# HighLevel.net
KiCad netlist of a schematic drawn in EAGLE
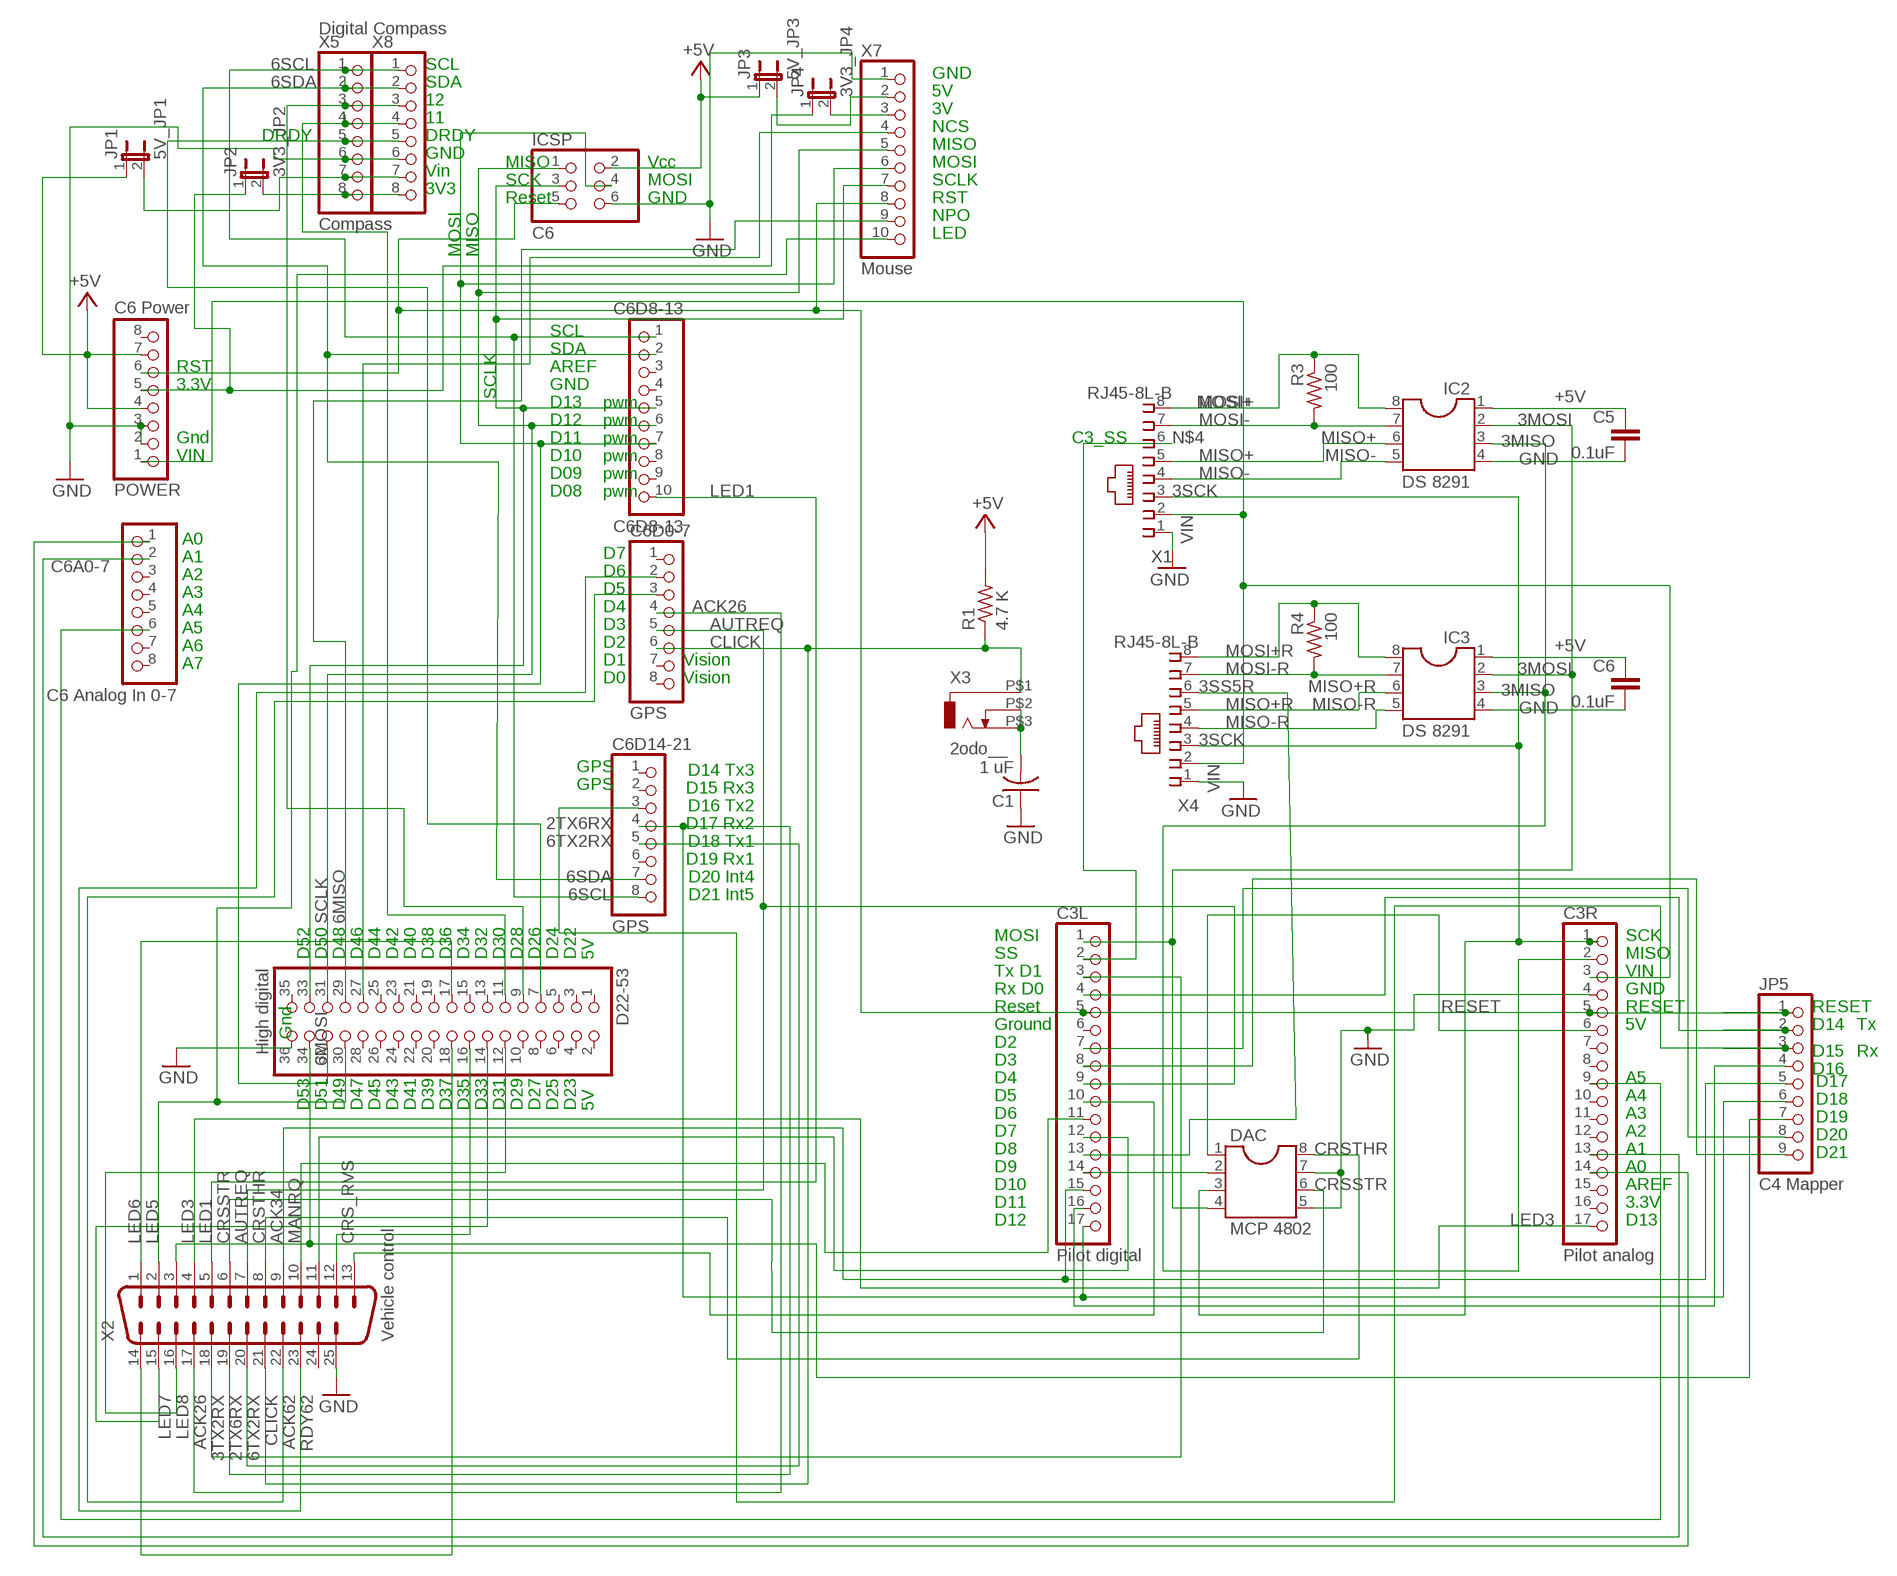
[diagram p0: schematic, sheet 1]

(export (version "E")
  (design (tool "Eeschema 10.0.6"))
  (components
    (comp (ref "C1")
      (value "1 uF")
      (footprint "eagle-import:C025-030X050")
      (libsource (lib "eagle-import") (part "C-US025-030X050"))
    )
    (comp (ref "C3L")
      (value "Pilot digital")
      (footprint "eagle-import:1X17")
      (libsource (lib "eagle-import") (part "PINHD-1X17"))
    )
    (comp (ref "C3R")
      (value "Pilot analog")
      (footprint "eagle-import:1X17")
      (libsource (lib "eagle-import") (part "PINHD-1X17"))
    )
    (comp (ref "C5")
      (value "0.1uF")
      (footprint "eagle-import:C2.5-2")
      (libsource (lib "eagle-import") (part "C2.5/2"))
    )
    (comp (ref "C6")
      (value "0.1uF")
      (footprint "eagle-import:C2.5-2")
      (libsource (lib "eagle-import") (part "C2.5/2"))
    )
    (comp (ref "C6A0-7")
      (value "C6 Analog In 0-7")
      (footprint "eagle-import:1X08")
      (libsource (lib "eagle-import") (part "PINHD-1X8"))
    )
    (comp (ref "C6D0-7")
      (value "GPS")
      (footprint "eagle-import:1X08")
      (libsource (lib "eagle-import") (part "PINHD-1X8"))
    )
    (comp (ref "C6D8-13")
      (value "C6D8-13")
      (footprint "eagle-import:1X10")
      (libsource (lib "eagle-import") (part "PINHD-1X10"))
    )
    (comp (ref "C6D14-21")
      (value "GPS")
      (footprint "eagle-import:1X08")
      (libsource (lib "eagle-import") (part "PINHD-1X8"))
    )
    (comp (ref "D22-53")
      (value "High digital")
      (footprint "eagle-import:2X18")
      (libsource (lib "eagle-import") (part "PINHD-2X18"))
    )
    (comp (ref "DAC")
      (value "MCP 4802")
      (footprint "eagle-import:DIL08")
      (libsource (lib "eagle-import") (part "DIL8"))
    )
    (comp (ref "IC2")
      (value "DS 8291")
      (footprint "eagle-import:DIL08")
      (libsource (lib "eagle-import") (part "DIL8"))
    )
    (comp (ref "IC3")
      (value "DS 8291")
      (footprint "eagle-import:DIL08")
      (libsource (lib "eagle-import") (part "DIL8"))
    )
    (comp (ref "ICSP")
      (value "C6")
      (footprint "eagle-import:2X03")
      (libsource (lib "eagle-import") (part "PINHD-2X3"))
    )
    (comp (ref "JP1")
      (value "5V_JP1")
      (footprint "eagle-import:JP1")
      (libsource (lib "eagle-import") (part "JP1E"))
    )
    (comp (ref "JP2")
      (value "3V3_JP2")
      (footprint "eagle-import:JP1")
      (libsource (lib "eagle-import") (part "JP1E"))
    )
    (comp (ref "JP3")
      (value "5V_JP3")
      (footprint "eagle-import:JP1")
      (libsource (lib "eagle-import") (part "JP1E"))
    )
    (comp (ref "JP4")
      (value "3V3_JP4")
      (footprint "eagle-import:JP1")
      (libsource (lib "eagle-import") (part "JP1E"))
    )
    (comp (ref "JP5")
      (value "C4 Mapper")
      (footprint "eagle-import:1X09")
      (libsource (lib "eagle-import") (part "PINHD-1X9"))
    )
    (comp (ref "POWER")
      (value "C6 Power")
      (footprint "eagle-import:1X08")
      (libsource (lib "eagle-import") (part "PINHD-1X8"))
    )
    (comp (ref "R1")
      (value "4.7 K")
      (footprint "eagle-import:0207_10")
      (libsource (lib "eagle-import") (part "R-US_0207/10"))
    )
    (comp (ref "R3")
      (value "100")
      (footprint "eagle-import:0204_5")
      (libsource (lib "eagle-import") (part "resistor_R-US_0204/5"))
    )
    (comp (ref "R4")
      (value "100")
      (footprint "eagle-import:0204_5")
      (libsource (lib "eagle-import") (part "resistor_R-US_0204/5"))
    )
    (comp (ref "X1")
      (value "RJ45-8L-B")
      (footprint "eagle-import:RJ45-NO-SHIELD")
      (fields (field (name "MF") "TYCO ELECTRONICS"))
      (libsource (lib "eagle-import") (part "RJ45-8L-B"))
    )
    (comp (ref "X2")
      (value "Vehicle control")
      (footprint "eagle-import:M25H")
      (libsource (lib "eagle-import") (part "M25H"))
    )
    (comp (ref "X3")
      (value "2odo__")
      (footprint "eagle-import:ODO_JACK")
      (libsource (lib "eagle-import") (part "ODO_JACK"))
    )
    (comp (ref "X4")
      (value "RJ45-8L-B")
      (footprint "eagle-import:RJ45-NO-SHIELD")
      (fields (field (name "MF") "TYCO ELECTRONICS"))
      (libsource (lib "eagle-import") (part "RJ45-8L-B"))
    )
    (comp (ref "X5")
      (value "Compass")
      (footprint "eagle-import:1X08")
      (libsource (lib "eagle-import") (part "PINHD-1X8"))
    )
    (comp (ref "X7")
      (value "Mouse")
      (footprint "eagle-import:1X10")
      (libsource (lib "eagle-import") (part "PINHD-1X10"))
    )
    (comp (ref "X8")
      (value "Digital Compass")
      (footprint "eagle-import:1X08")
      (libsource (lib "eagle-import") (part "PINHD-1X8"))
    )
  )
  (nets
    (net (code "1") (name "+5V") (class "Default")
      (node (ref "C5") (pin "1") (pinfunction "1_1") (pintype "passive"))
      (node (ref "C6") (pin "1") (pinfunction "1_1") (pintype "passive"))
      (node (ref "IC2") (pin "1") (pinfunction "1_1") (pintype "passive"))
      (node (ref "IC3") (pin "1") (pinfunction "1_1") (pintype "passive"))
      (node (ref "ICSP") (pin "2") (pinfunction "2_2") (pintype "passive"))
      (node (ref "JP1") (pin "1") (pinfunction "1_1") (pintype "passive"))
      (node (ref "JP3") (pin "1") (pinfunction "1_1") (pintype "passive"))
      (node (ref "POWER") (pin "4") (pinfunction "4_4") (pintype "passive"))
      (node (ref "POWER") (pin "7") (pinfunction "7_7") (pintype "passive"))
      (node (ref "R1") (pin "2") (pinfunction "2_2") (pintype "passive"))
    )
    (net (code "2") (name "2TX6RX") (class "Default")
      (node (ref "C3L") (pin "17") (pinfunction "17_17") (pintype "passive"))
      (node (ref "C6D14-21") (pin "4") (pinfunction "4_4") (pintype "passive"))
      (node (ref "JP5") (pin "6") (pinfunction "6_6") (pintype "passive"))
      (node (ref "X2") (pin "19") (pinfunction "19_19") (pintype "passive"))
    )
    (net (code "3") (name "3MISO") (class "Default")
      (node (ref "C3R") (pin "2") (pinfunction "2_2") (pintype "passive"))
      (node (ref "IC2") (pin "3") (pinfunction "3_3") (pintype "passive"))
      (node (ref "IC3") (pin "3") (pinfunction "3_3") (pintype "passive"))
    )
    (net (code "4") (name "3MOSI") (class "Default")
      (node (ref "C3L") (pin "1") (pinfunction "1_1") (pintype "passive"))
      (node (ref "DAC") (pin "4") (pinfunction "4_4") (pintype "passive"))
      (node (ref "IC2") (pin "2") (pinfunction "2_2") (pintype "passive"))
      (node (ref "IC3") (pin "2") (pinfunction "2_2") (pintype "passive"))
    )
    (net (code "5") (name "3SCK") (class "Default")
      (node (ref "C3R") (pin "1") (pinfunction "1_1") (pintype "passive"))
      (node (ref "DAC") (pin "3") (pinfunction "3_3") (pintype "passive"))
      (node (ref "X1") (pin "3") (pinfunction "3_3") (pintype "passive"))
      (node (ref "X4") (pin "3") (pinfunction "3_3") (pintype "passive"))
    )
    (net (code "6") (name "3SS5R") (class "Default")
      (node (ref "C3L") (pin "13") (pinfunction "13_13") (pintype "passive"))
      (node (ref "X4") (pin "6") (pinfunction "6_6") (pintype "passive"))
    )
    (net (code "7") (name "3TX2RX") (class "Default")
      (node (ref "C3L") (pin "3") (pinfunction "3_3") (pintype "passive"))
      (node (ref "X2") (pin "18") (pinfunction "18_18") (pintype "passive"))
    )
    (net (code "8") (name "6MISO") (class "Default")
      (node (ref "C6D8-13") (pin "6") (pinfunction "6_6") (pintype "passive"))
      (node (ref "D22-53") (pin "31") (pinfunction "31_31") (pintype "passive"))
      (node (ref "ICSP") (pin "1") (pinfunction "1_1") (pintype "passive"))
      (node (ref "X7") (pin "5") (pinfunction "5_5") (pintype "passive"))
    )
    (net (code "9") (name "6MOSI") (class "Default")
      (node (ref "C6D8-13") (pin "7") (pinfunction "7_7") (pintype "passive"))
      (node (ref "D22-53") (pin "32") (pinfunction "32_32") (pintype "passive"))
      (node (ref "ICSP") (pin "4") (pinfunction "4_4") (pintype "passive"))
      (node (ref "X7") (pin "6") (pinfunction "6_6") (pintype "passive"))
    )
    (net (code "10") (name "6SCL") (class "Default")
      (node (ref "C6D14-21") (pin "8") (pinfunction "8_8") (pintype "passive"))
      (node (ref "C6D8-13") (pin "1") (pinfunction "1_1") (pintype "passive"))
      (node (ref "X5") (pin "1") (pinfunction "1_1") (pintype "passive"))
      (node (ref "X8") (pin "1") (pinfunction "1_1") (pintype "passive"))
    )
    (net (code "11") (name "6SDA") (class "Default")
      (node (ref "C6D14-21") (pin "7") (pinfunction "7_7") (pintype "passive"))
      (node (ref "C6D8-13") (pin "2") (pinfunction "2_2") (pintype "passive"))
      (node (ref "X5") (pin "2") (pinfunction "2_2") (pintype "passive"))
      (node (ref "X8") (pin "2") (pinfunction "2_2") (pintype "passive"))
    )
    (net (code "12") (name "6TX2RX") (class "Default")
      (node (ref "C6D14-21") (pin "5") (pinfunction "5_5") (pintype "passive"))
      (node (ref "X2") (pin "20") (pinfunction "20_20") (pintype "passive"))
    )
    (net (code "13") (name "ACK26") (class "Default")
      (node (ref "C6D0-7") (pin "4") (pinfunction "4_4") (pintype "passive"))
      (node (ref "X2") (pin "17") (pinfunction "17_17") (pintype "passive"))
    )
    (net (code "14") (name "ACK34") (class "Default")
      (node (ref "C3L") (pin "15") (pinfunction "15_15") (pintype "passive"))
      (node (ref "JP5") (pin "5") (pinfunction "5_5") (pintype "passive"))
      (node (ref "X2") (pin "9") (pinfunction "9_9") (pintype "passive"))
    )
    (net (code "15") (name "ACK62") (class "Default")
      (node (ref "C6D0-7") (pin "3") (pinfunction "3_3") (pintype "passive"))
      (node (ref "X2") (pin "22") (pinfunction "22_22") (pintype "passive"))
    )
    (net (code "16") (name "AUTREQ") (class "Default")
      (node (ref "C3L") (pin "9") (pinfunction "9_9") (pintype "passive"))
      (node (ref "C6D0-7") (pin "5") (pinfunction "5_5") (pintype "passive"))
      (node (ref "X2") (pin "7") (pinfunction "7_7") (pintype "passive"))
    )
    (net (code "17") (name "CLICK") (class "Default")
      (node (ref "C6D0-7") (pin "6") (pinfunction "6_6") (pintype "passive"))
      (node (ref "R1") (pin "1") (pinfunction "1_1") (pintype "passive"))
      (node (ref "X2") (pin "21") (pinfunction "21_21") (pintype "passive"))
      (node (ref "X3") (pin "P$1") (pinfunction "1_P$1") (pintype "passive"))
    )
    (net (code "18") (name "CRSSTR") (class "Default")
      (node (ref "DAC") (pin "6") (pinfunction "6_6") (pintype "passive"))
      (node (ref "X2") (pin "6") (pinfunction "6_6") (pintype "passive"))
    )
    (net (code "19") (name "CRSTHR") (class "Default")
      (node (ref "DAC") (pin "8") (pinfunction "8_8") (pintype "passive"))
      (node (ref "X2") (pin "8") (pinfunction "8_8") (pintype "passive"))
    )
    (net (code "20") (name "CRS_RVS") (class "Default")
      (node (ref "C3L") (pin "10") (pinfunction "10_10") (pintype "passive"))
      (node (ref "X2") (pin "13") (pinfunction "13_13") (pintype "passive"))
    )
    (net (code "21") (name "GND") (class "Default")
      (node (ref "C1") (pin "1") (pinfunction "1_1") (pintype "passive"))
      (node (ref "C3R") (pin "4") (pinfunction "4_4") (pintype "passive"))
      (node (ref "C5") (pin "2") (pinfunction "2_2") (pintype "passive"))
      (node (ref "C6") (pin "2") (pinfunction "2_2") (pintype "passive"))
      (node (ref "D22-53") (pin "36") (pinfunction "36_36") (pintype "passive"))
      (node (ref "DAC") (pin "5") (pinfunction "5_5") (pintype "passive"))
      (node (ref "DAC") (pin "7") (pinfunction "7_7") (pintype "passive"))
      (node (ref "IC2") (pin "4") (pinfunction "4_4") (pintype "passive"))
      (node (ref "IC3") (pin "4") (pinfunction "4_4") (pintype "passive"))
      (node (ref "ICSP") (pin "6") (pinfunction "6_6") (pintype "passive"))
      (node (ref "POWER") (pin "2") (pinfunction "2_2") (pintype "passive"))
      (node (ref "POWER") (pin "3") (pinfunction "3_3") (pintype "passive"))
      (node (ref "X1") (pin "1") (pinfunction "1_1") (pintype "passive"))
      (node (ref "X2") (pin "25") (pinfunction "25_25") (pintype "passive"))
      (node (ref "X4") (pin "1") (pinfunction "1_1") (pintype "passive"))
      (node (ref "X5") (pin "6") (pinfunction "6_6") (pintype "passive"))
      (node (ref "X7") (pin "1") (pinfunction "1_1") (pintype "passive"))
      (node (ref "X8") (pin "6") (pinfunction "6_6") (pintype "passive"))
    )
    (net (code "22") (name "LED1") (class "Default")
      (node (ref "C6D8-13") (pin "10") (pinfunction "10_10") (pintype "passive"))
      (node (ref "X2") (pin "5") (pinfunction "5_5") (pintype "passive"))
    )
    (net (code "23") (name "LED3") (class "Default")
      (node (ref "C3R") (pin "17") (pinfunction "17_17") (pintype "passive"))
      (node (ref "X2") (pin "4") (pinfunction "4_4") (pintype "passive"))
    )
    (net (code "24") (name "LED5") (class "Default")
      (node (ref "D22-53") (pin "30") (pinfunction "30_30") (pintype "passive"))
      (node (ref "X2") (pin "2") (pinfunction "2_2") (pintype "passive"))
      (node (ref "X7") (pin "10") (pinfunction "10_10") (pintype "passive"))
    )
    (net (code "25") (name "LED6") (class "Default")
      (node (ref "D22-53") (pin "17") (pinfunction "17_17") (pintype "passive"))
      (node (ref "X2") (pin "1") (pinfunction "1_1") (pintype "passive"))
    )
    (net (code "26") (name "LED7") (class "Default")
      (node (ref "D22-53") (pin "14") (pinfunction "14_14") (pintype "passive"))
      (node (ref "X2") (pin "15") (pinfunction "15_15") (pintype "passive"))
    )
    (net (code "27") (name "LED8") (class "Default")
      (node (ref "D22-53") (pin "12") (pinfunction "12_12") (pintype "passive"))
      (node (ref "X2") (pin "16") (pinfunction "16_16") (pintype "passive"))
    )
    (net (code "28") (name "MANRQ") (class "Default")
      (node (ref "C3L") (pin "11") (pinfunction "11_11") (pintype "passive"))
      (node (ref "X2") (pin "10") (pinfunction "10_10") (pintype "passive"))
    )
    (net (code "29") (name "MISO+") (class "Default")
      (node (ref "IC2") (pin "6") (pinfunction "6_6") (pintype "passive"))
      (node (ref "X1") (pin "5") (pinfunction "5_5") (pintype "passive"))
    )
    (net (code "30") (name "MISO+R") (class "Default")
      (node (ref "IC3") (pin "6") (pinfunction "6_6") (pintype "passive"))
      (node (ref "X4") (pin "5") (pinfunction "5_5") (pintype "passive"))
    )
    (net (code "31") (name "MISO-") (class "Default")
      (node (ref "IC2") (pin "5") (pinfunction "5_5") (pintype "passive"))
      (node (ref "X1") (pin "4") (pinfunction "4_4") (pintype "passive"))
    )
    (net (code "32") (name "MISO-R") (class "Default")
      (node (ref "IC3") (pin "5") (pinfunction "5_5") (pintype "passive"))
      (node (ref "X4") (pin "4") (pinfunction "4_4") (pintype "passive"))
    )
    (net (code "33") (name "MOSI+") (class "Default")
      (node (ref "IC2") (pin "8") (pinfunction "8_8") (pintype "passive"))
      (node (ref "R3") (pin "1") (pinfunction "1_1") (pintype "passive"))
      (node (ref "X1") (pin "8") (pinfunction "8_8") (pintype "passive"))
    )
    (net (code "34") (name "MOSI+R") (class "Default")
      (node (ref "IC3") (pin "8") (pinfunction "8_8") (pintype "passive"))
      (node (ref "R4") (pin "1") (pinfunction "1_1") (pintype "passive"))
      (node (ref "X4") (pin "8") (pinfunction "8_8") (pintype "passive"))
    )
    (net (code "35") (name "MOSI-") (class "Default")
      (node (ref "IC2") (pin "7") (pinfunction "7_7") (pintype "passive"))
      (node (ref "R3") (pin "2") (pinfunction "2_2") (pintype "passive"))
      (node (ref "X1") (pin "7") (pinfunction "7_7") (pintype "passive"))
    )
    (net (code "36") (name "MOSI-R") (class "Default")
      (node (ref "IC3") (pin "7") (pinfunction "7_7") (pintype "passive"))
      (node (ref "R4") (pin "2") (pinfunction "2_2") (pintype "passive"))
      (node (ref "X4") (pin "7") (pinfunction "7_7") (pintype "passive"))
    )
    (net (code "37") (name "N$4") (class "Default")
      (node (ref "C3L") (pin "2") (pinfunction "2_2") (pintype "passive"))
      (node (ref "X1") (pin "6") (pinfunction "6_6") (pintype "passive"))
    )
    (net (code "38") (name "Net-(C3L-Pad4)") (class "Default")
      (node (ref "C3L") (pin "4") (pinfunction "4_4") (pintype "passive"))
      (node (ref "JP5") (pin "2") (pinfunction "2_2") (pintype "passive"))
    )
    (net (code "39") (name "Net-(C3L-Pad7)") (class "Default")
      (node (ref "C3L") (pin "7") (pinfunction "7_7") (pintype "passive"))
      (node (ref "JP5") (pin "8") (pinfunction "8_8") (pintype "passive"))
    )
    (net (code "40") (name "Net-(C3L-Pad8)") (class "Default")
      (node (ref "C3L") (pin "8") (pinfunction "8_8") (pintype "passive"))
      (node (ref "JP5") (pin "9") (pinfunction "9_9") (pintype "passive"))
    )
    (net (code "41") (name "Net-(C3L-Pad12)") (class "Default")
      (node (ref "C3L") (pin "12") (pinfunction "12_12") (pintype "passive"))
      (node (ref "X2") (pin "11") (pinfunction "11_11") (pintype "passive"))
    )
    (net (code "42") (name "Net-(C3L-Pad14)") (class "Default")
      (node (ref "C3L") (pin "14") (pinfunction "14_14") (pintype "passive"))
      (node (ref "DAC") (pin "2") (pinfunction "2_2") (pintype "passive"))
    )
    (net (code "43") (name "Net-(C3L-Pad16)") (class "Default")
      (node (ref "C3L") (pin "16") (pinfunction "16_16") (pintype "passive"))
      (node (ref "JP5") (pin "4") (pinfunction "4_4") (pintype "passive"))
    )
    (net (code "44") (name "Net-(C3R-Pad6)") (class "Default")
      (node (ref "C3R") (pin "6") (pinfunction "6_6") (pintype "passive"))
      (node (ref "DAC") (pin "1") (pinfunction "1_1") (pintype "passive"))
    )
    (net (code "45") (name "Net-(C3R-Pad9)") (class "Default")
      (node (ref "C3R") (pin "9") (pinfunction "9_9") (pintype "passive"))
      (node (ref "C6A0-7") (pin "6") (pinfunction "6_6") (pintype "passive"))
    )
    (net (code "46") (name "Net-(C3R-Pad13)") (class "Default")
      (node (ref "C3R") (pin "13") (pinfunction "13_13") (pintype "passive"))
      (node (ref "C6A0-7") (pin "2") (pinfunction "2_2") (pintype "passive"))
    )
    (net (code "47") (name "Net-(C3R-Pad14)") (class "Default")
      (node (ref "C3R") (pin "14") (pinfunction "14_14") (pintype "passive"))
      (node (ref "C6A0-7") (pin "1") (pinfunction "1_1") (pintype "passive"))
    )
    (net (code "48") (name "Net-(C6D14-21-Pad3)") (class "Default")
      (node (ref "C6D14-21") (pin "3") (pinfunction "3_3") (pintype "passive"))
      (node (ref "JP5") (pin "3") (pinfunction "3_3") (pintype "passive"))
    )
    (net (code "49") (name "Net-(D22-53-Pad7)") (class "Default")
      (node (ref "D22-53") (pin "7") (pinfunction "7_7") (pintype "passive"))
      (node (ref "X5") (pin "5") (pinfunction "5_5") (pintype "passive"))
      (node (ref "X8") (pin "5") (pinfunction "5_5") (pintype "passive"))
    )
    (net (code "50") (name "Net-(D22-53-Pad9)") (class "Default")
      (node (ref "D22-53") (pin "9") (pinfunction "9_9") (pintype "passive"))
      (node (ref "X5") (pin "3") (pinfunction "3_3") (pintype "passive"))
      (node (ref "X8") (pin "3") (pinfunction "3_3") (pintype "passive"))
    )
    (net (code "51") (name "Net-(D22-53-Pad11)") (class "Default")
      (node (ref "D22-53") (pin "11") (pinfunction "11_11") (pintype "passive"))
      (node (ref "X5") (pin "4") (pinfunction "4_4") (pintype "passive"))
      (node (ref "X8") (pin "4") (pinfunction "4_4") (pintype "passive"))
    )
    (net (code "52") (name "Net-(D22-53-Pad16)") (class "Default")
      (node (ref "D22-53") (pin "16") (pinfunction "16_16") (pintype "passive"))
      (node (ref "X2") (pin "12") (pinfunction "12_12") (pintype "passive"))
    )
    (net (code "53") (name "Net-(D22-53-Pad18)") (class "Default")
      (node (ref "D22-53") (pin "18") (pinfunction "18_18") (pintype "passive"))
      (node (ref "X2") (pin "14") (pinfunction "14_14") (pintype "passive"))
    )
    (net (code "54") (name "Net-(D22-53-Pad27)") (class "Default")
      (node (ref "D22-53") (pin "27") (pinfunction "27_27") (pintype "passive"))
      (node (ref "X7") (pin "4") (pinfunction "4_4") (pintype "passive"))
    )
    (net (code "55") (name "Net-(D22-53-Pad29)") (class "Default")
      (node (ref "D22-53") (pin "29") (pinfunction "29_29") (pintype "passive"))
      (node (ref "X7") (pin "9") (pinfunction "9_9") (pintype "passive"))
    )
    (net (code "56") (name "Net-(D22-53-Pad34)") (class "Default")
      (node (ref "D22-53") (pin "34") (pinfunction "34_34") (pintype "passive"))
      (node (ref "JP5") (pin "7") (pinfunction "7_7") (pintype "passive"))
      (node (ref "X2") (pin "3") (pinfunction "3_3") (pintype "passive"))
    )
    (net (code "57") (name "Net-(JP1-Pad2)") (class "Default")
      (node (ref "JP1") (pin "2") (pinfunction "2_2") (pintype "passive"))
      (node (ref "X5") (pin "7") (pinfunction "7_7") (pintype "passive"))
      (node (ref "X8") (pin "7") (pinfunction "7_7") (pintype "passive"))
    )
    (net (code "58") (name "Net-(JP2-Pad1)") (class "Default")
      (node (ref "JP2") (pin "1") (pinfunction "1_1") (pintype "passive"))
      (node (ref "JP4") (pin "1") (pinfunction "1_1") (pintype "passive"))
      (node (ref "POWER") (pin "5") (pinfunction "5_5") (pintype "passive"))
    )
    (net (code "59") (name "Net-(JP2-Pad2)") (class "Default")
      (node (ref "JP2") (pin "2") (pinfunction "2_2") (pintype "passive"))
      (node (ref "X5") (pin "8") (pinfunction "8_8") (pintype "passive"))
      (node (ref "X8") (pin "8") (pinfunction "8_8") (pintype "passive"))
    )
    (net (code "60") (name "Net-(JP3-Pad2)") (class "Default")
      (node (ref "JP3") (pin "2") (pinfunction "2_2") (pintype "passive"))
      (node (ref "X7") (pin "2") (pinfunction "2_2") (pintype "passive"))
    )
    (net (code "61") (name "Net-(JP4-Pad2)") (class "Default")
      (node (ref "JP4") (pin "2") (pinfunction "2_2") (pintype "passive"))
      (node (ref "X7") (pin "3") (pinfunction "3_3") (pintype "passive"))
    )
    (net (code "62") (name "Net-(X3-2)") (class "Default")
      (node (ref "C1") (pin "2") (pinfunction "2_2") (pintype "passive"))
      (node (ref "X3") (pin "P$2") (pinfunction "2_P$2") (pintype "passive"))
      (node (ref "X3") (pin "P$3") (pinfunction "3_P$3") (pintype "passive"))
    )
    (net (code "63") (name "RDY62") (class "Default")
      (node (ref "C6D0-7") (pin "2") (pinfunction "2_2") (pintype "passive"))
      (node (ref "X2") (pin "23") (pinfunction "23_23") (pintype "passive"))
    )
    (net (code "64") (name "RESET") (class "Default")
      (node (ref "C3L") (pin "5") (pinfunction "5_5") (pintype "passive"))
      (node (ref "C3R") (pin "5") (pinfunction "5_5") (pintype "passive"))
      (node (ref "ICSP") (pin "5") (pinfunction "5_5") (pintype "passive"))
      (node (ref "JP5") (pin "1") (pinfunction "1_1") (pintype "passive"))
      (node (ref "POWER") (pin "6") (pinfunction "6_6") (pintype "passive"))
      (node (ref "X7") (pin "8") (pinfunction "8_8") (pintype "passive"))
    )
    (net (code "65") (name "SCLK") (class "Default")
      (node (ref "C6D8-13") (pin "5") (pinfunction "5_5") (pintype "passive"))
      (node (ref "D22-53") (pin "33") (pinfunction "33_33") (pintype "passive"))
      (node (ref "ICSP") (pin "3") (pinfunction "3_3") (pintype "passive"))
      (node (ref "X7") (pin "7") (pinfunction "7_7") (pintype "passive"))
    )
    (net (code "66") (name "VIN") (class "Default")
      (node (ref "C3R") (pin "3") (pinfunction "3_3") (pintype "passive"))
      (node (ref "POWER") (pin "1") (pinfunction "1_1") (pintype "passive"))
      (node (ref "X1") (pin "2") (pinfunction "2_2") (pintype "passive"))
      (node (ref "X4") (pin "2") (pinfunction "2_2") (pintype "passive"))
    )
    (net (code "67") (name "unconnected-(C3L-Pad6)") (class "Default")
      (node (ref "C3L") (pin "6") (pinfunction "6_6") (pintype "passive"))
    )
    (net (code "68") (name "unconnected-(C3R-Pad7)") (class "Default")
      (node (ref "C3R") (pin "7") (pinfunction "7_7") (pintype "passive"))
    )
    (net (code "69") (name "unconnected-(C3R-Pad8)") (class "Default")
      (node (ref "C3R") (pin "8") (pinfunction "8_8") (pintype "passive"))
    )
    (net (code "70") (name "unconnected-(C3R-Pad10)") (class "Default")
      (node (ref "C3R") (pin "10") (pinfunction "10_10") (pintype "passive"))
    )
    (net (code "71") (name "unconnected-(C3R-Pad11)") (class "Default")
      (node (ref "C3R") (pin "11") (pinfunction "11_11") (pintype "passive"))
    )
    (net (code "72") (name "unconnected-(C3R-Pad12)") (class "Default")
      (node (ref "C3R") (pin "12") (pinfunction "12_12") (pintype "passive"))
    )
    (net (code "73") (name "unconnected-(C3R-Pad15)") (class "Default")
      (node (ref "C3R") (pin "15") (pinfunction "15_15") (pintype "passive"))
    )
    (net (code "74") (name "unconnected-(C3R-Pad16)") (class "Default")
      (node (ref "C3R") (pin "16") (pinfunction "16_16") (pintype "passive"))
    )
    (net (code "75") (name "unconnected-(C6A0-7-Pad3)") (class "Default")
      (node (ref "C6A0-7") (pin "3") (pinfunction "3_3") (pintype "passive"))
    )
    (net (code "76") (name "unconnected-(C6A0-7-Pad4)") (class "Default")
      (node (ref "C6A0-7") (pin "4") (pinfunction "4_4") (pintype "passive"))
    )
    (net (code "77") (name "unconnected-(C6A0-7-Pad5)") (class "Default")
      (node (ref "C6A0-7") (pin "5") (pinfunction "5_5") (pintype "passive"))
    )
    (net (code "78") (name "unconnected-(C6A0-7-Pad7)") (class "Default")
      (node (ref "C6A0-7") (pin "7") (pinfunction "7_7") (pintype "passive"))
    )
    (net (code "79") (name "unconnected-(C6A0-7-Pad8)") (class "Default")
      (node (ref "C6A0-7") (pin "8") (pinfunction "8_8") (pintype "passive"))
    )
    (net (code "80") (name "unconnected-(C6D0-7-Pad1)") (class "Default")
      (node (ref "C6D0-7") (pin "1") (pinfunction "1_1") (pintype "passive"))
    )
    (net (code "81") (name "unconnected-(C6D0-7-Pad7)") (class "Default")
      (node (ref "C6D0-7") (pin "7") (pinfunction "7_7") (pintype "passive"))
    )
    (net (code "82") (name "unconnected-(C6D0-7-Pad8)") (class "Default")
      (node (ref "C6D0-7") (pin "8") (pinfunction "8_8") (pintype "passive"))
    )
    (net (code "83") (name "unconnected-(C6D8-13-Pad3)") (class "Default")
      (node (ref "C6D8-13") (pin "3") (pinfunction "3_3") (pintype "passive"))
    )
    (net (code "84") (name "unconnected-(C6D8-13-Pad4)") (class "Default")
      (node (ref "C6D8-13") (pin "4") (pinfunction "4_4") (pintype "passive"))
    )
    (net (code "85") (name "unconnected-(C6D8-13-Pad8)") (class "Default")
      (node (ref "C6D8-13") (pin "8") (pinfunction "8_8") (pintype "passive"))
    )
    (net (code "86") (name "unconnected-(C6D8-13-Pad9)") (class "Default")
      (node (ref "C6D8-13") (pin "9") (pinfunction "9_9") (pintype "passive"))
    )
    (net (code "87") (name "unconnected-(C6D14-21-Pad1)") (class "Default")
      (node (ref "C6D14-21") (pin "1") (pinfunction "1_1") (pintype "passive"))
    )
    (net (code "88") (name "unconnected-(C6D14-21-Pad2)") (class "Default")
      (node (ref "C6D14-21") (pin "2") (pinfunction "2_2") (pintype "passive"))
    )
    (net (code "89") (name "unconnected-(C6D14-21-Pad6)") (class "Default")
      (node (ref "C6D14-21") (pin "6") (pinfunction "6_6") (pintype "passive"))
    )
    (net (code "90") (name "unconnected-(D22-53-Pad1)") (class "Default")
      (node (ref "D22-53") (pin "1") (pinfunction "1_1") (pintype "passive"))
    )
    (net (code "91") (name "unconnected-(D22-53-Pad2)") (class "Default")
      (node (ref "D22-53") (pin "2") (pinfunction "2_2") (pintype "passive"))
    )
    (net (code "92") (name "unconnected-(D22-53-Pad3)") (class "Default")
      (node (ref "D22-53") (pin "3") (pinfunction "3_3") (pintype "passive"))
    )
    (net (code "93") (name "unconnected-(D22-53-Pad4)") (class "Default")
      (node (ref "D22-53") (pin "4") (pinfunction "4_4") (pintype "passive"))
    )
    (net (code "94") (name "unconnected-(D22-53-Pad5)") (class "Default")
      (node (ref "D22-53") (pin "5") (pinfunction "5_5") (pintype "passive"))
    )
    (net (code "95") (name "unconnected-(D22-53-Pad6)") (class "Default")
      (node (ref "D22-53") (pin "6") (pinfunction "6_6") (pintype "passive"))
    )
    (net (code "96") (name "unconnected-(D22-53-Pad8)") (class "Default")
      (node (ref "D22-53") (pin "8") (pinfunction "8_8") (pintype "passive"))
    )
    (net (code "97") (name "unconnected-(D22-53-Pad10)") (class "Default")
      (node (ref "D22-53") (pin "10") (pinfunction "10_10") (pintype "passive"))
    )
    (net (code "98") (name "unconnected-(D22-53-Pad13)") (class "Default")
      (node (ref "D22-53") (pin "13") (pinfunction "13_13") (pintype "passive"))
    )
    (net (code "99") (name "unconnected-(D22-53-Pad15)") (class "Default")
      (node (ref "D22-53") (pin "15") (pinfunction "15_15") (pintype "passive"))
    )
    (net (code "100") (name "unconnected-(D22-53-Pad19)") (class "Default")
      (node (ref "D22-53") (pin "19") (pinfunction "19_19") (pintype "passive"))
    )
    (net (code "101") (name "unconnected-(D22-53-Pad20)") (class "Default")
      (node (ref "D22-53") (pin "20") (pinfunction "20_20") (pintype "passive"))
    )
    (net (code "102") (name "unconnected-(D22-53-Pad21)") (class "Default")
      (node (ref "D22-53") (pin "21") (pinfunction "21_21") (pintype "passive"))
    )
    (net (code "103") (name "unconnected-(D22-53-Pad22)") (class "Default")
      (node (ref "D22-53") (pin "22") (pinfunction "22_22") (pintype "passive"))
    )
    (net (code "104") (name "unconnected-(D22-53-Pad23)") (class "Default")
      (node (ref "D22-53") (pin "23") (pinfunction "23_23") (pintype "passive"))
    )
    (net (code "105") (name "unconnected-(D22-53-Pad24)") (class "Default")
      (node (ref "D22-53") (pin "24") (pinfunction "24_24") (pintype "passive"))
    )
    (net (code "106") (name "unconnected-(D22-53-Pad25)") (class "Default")
      (node (ref "D22-53") (pin "25") (pinfunction "25_25") (pintype "passive"))
    )
    (net (code "107") (name "unconnected-(D22-53-Pad26)") (class "Default")
      (node (ref "D22-53") (pin "26") (pinfunction "26_26") (pintype "passive"))
    )
    (net (code "108") (name "unconnected-(D22-53-Pad28)") (class "Default")
      (node (ref "D22-53") (pin "28") (pinfunction "28_28") (pintype "passive"))
    )
    (net (code "109") (name "unconnected-(D22-53-Pad35)") (class "Default")
      (node (ref "D22-53") (pin "35") (pinfunction "35_35") (pintype "passive"))
    )
    (net (code "110") (name "unconnected-(POWER-Pad8)") (class "Default")
      (node (ref "POWER") (pin "8") (pinfunction "8_8") (pintype "passive"))
    )
    (net (code "111") (name "unconnected-(X2-Pad24)") (class "Default")
      (node (ref "X2") (pin "24") (pinfunction "24_24") (pintype "passive"))
    )
  )
)
